# PowerBoard.net
KiCad netlist of a schematic drawn in EAGLE
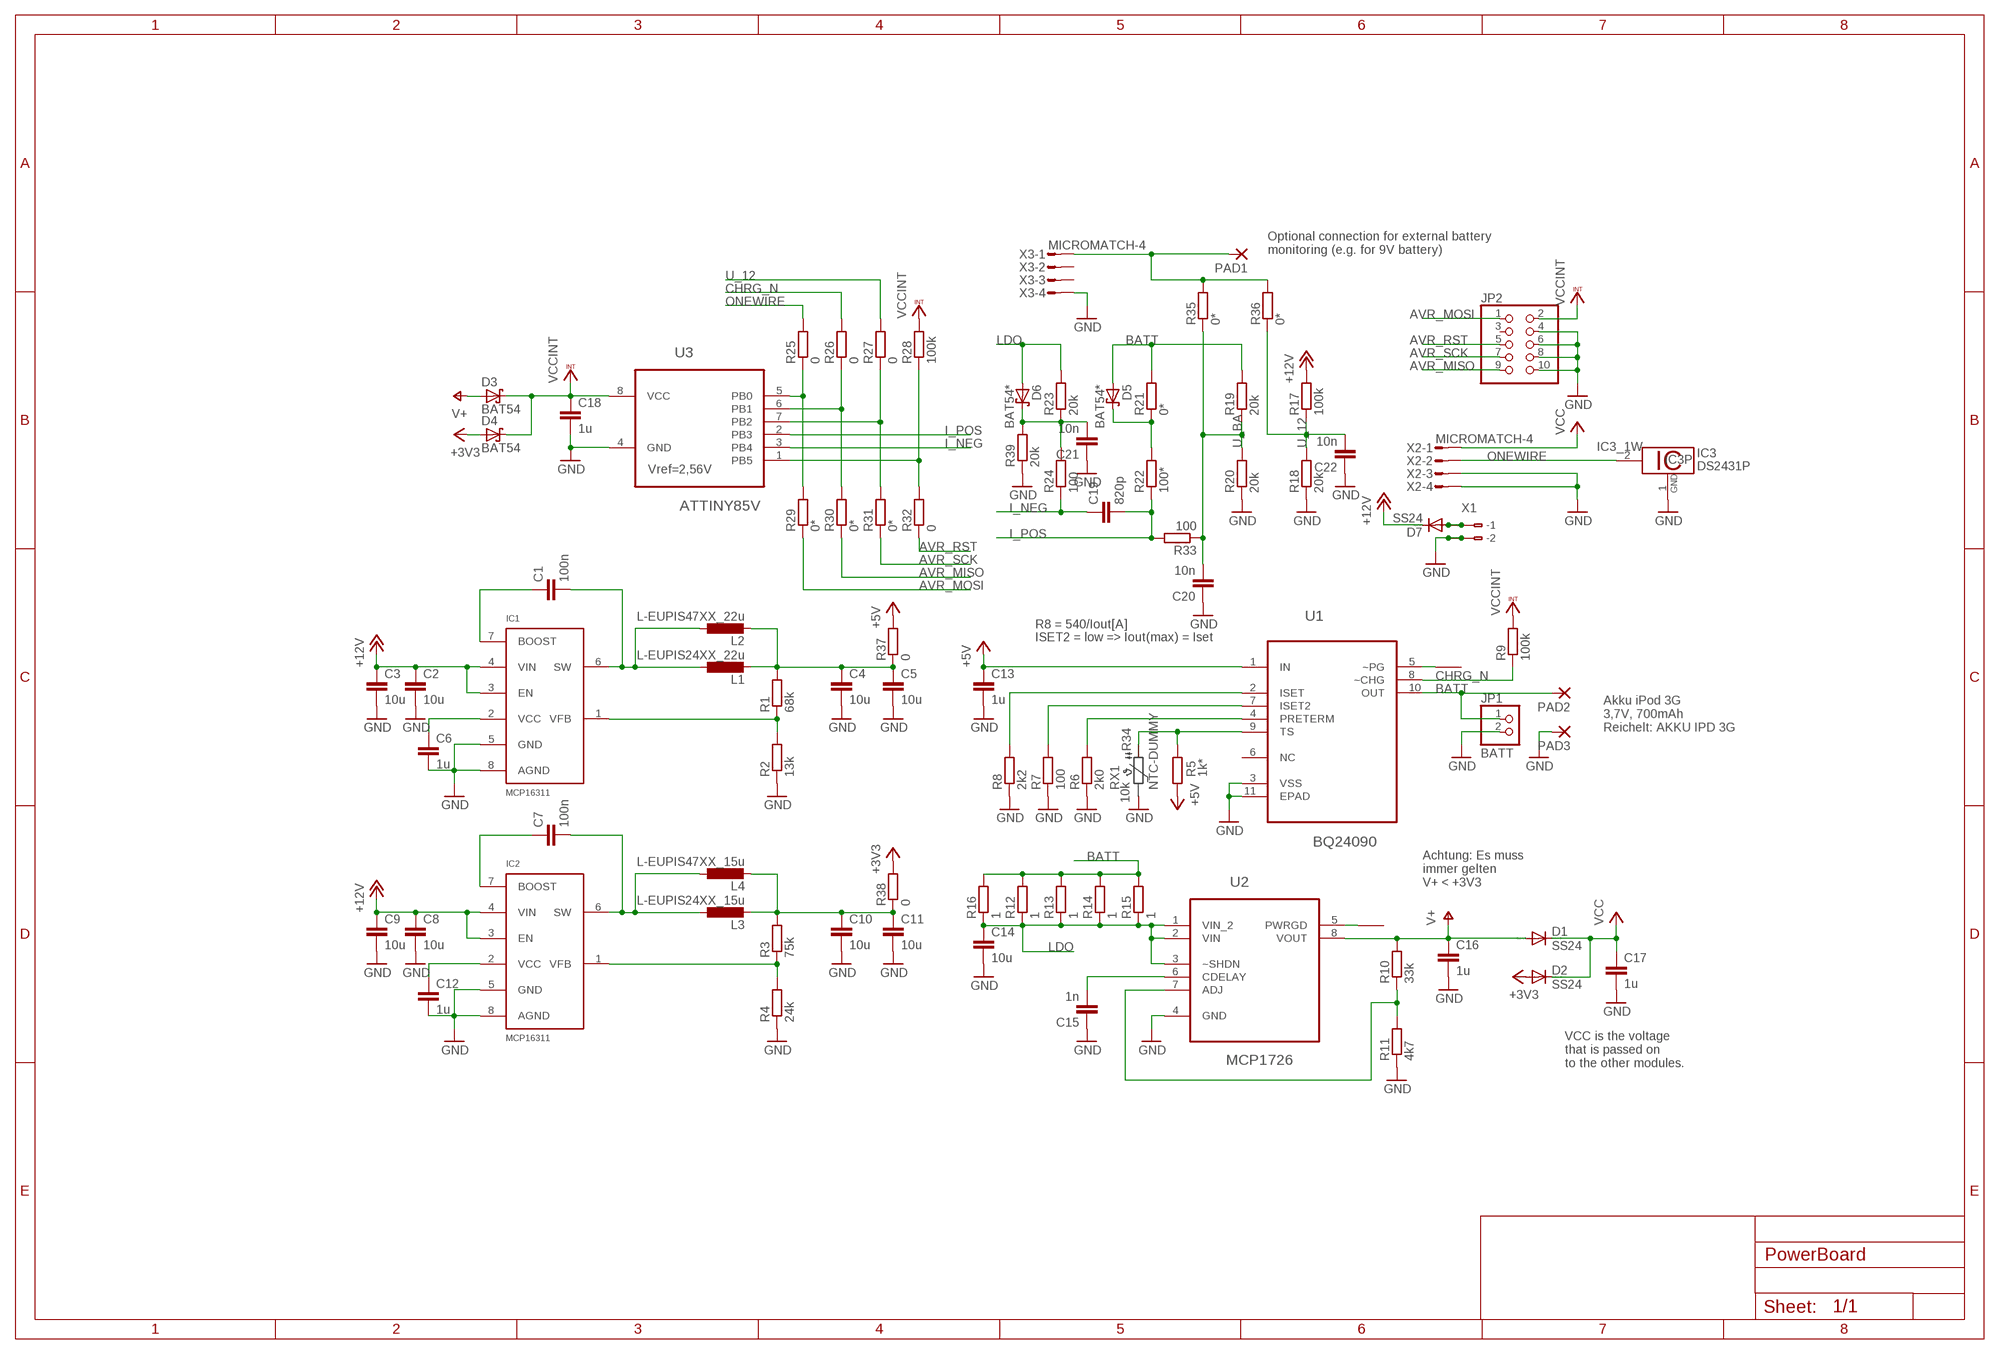
[diagram p0: schematic, sheet 1]

(export (version "E")
  (design (tool "Eeschema 10.0.6"))
  (components
    (comp (ref "C1")
      (value "100n")
      (footprint "eagle-import:C0603")
      (libsource (lib "eagle-import") (part "C-EUC0603"))
    )
    (comp (ref "C2")
      (value "10u")
      (footprint "eagle-import:C1210")
      (libsource (lib "eagle-import") (part "C-EUC1210"))
    )
    (comp (ref "C3")
      (value "10u")
      (footprint "eagle-import:C1210")
      (libsource (lib "eagle-import") (part "C-EUC1210"))
    )
    (comp (ref "C4")
      (value "10u")
      (footprint "eagle-import:C1210")
      (libsource (lib "eagle-import") (part "C-EUC1210"))
    )
    (comp (ref "C5")
      (value "10u")
      (footprint "eagle-import:C1210")
      (libsource (lib "eagle-import") (part "C-EUC1210"))
    )
    (comp (ref "C6")
      (value "1u")
      (footprint "eagle-import:C0603")
      (libsource (lib "eagle-import") (part "C-EUC0603"))
    )
    (comp (ref "C7")
      (value "100n")
      (footprint "eagle-import:C0603")
      (libsource (lib "eagle-import") (part "C-EUC0603"))
    )
    (comp (ref "C8")
      (value "10u")
      (footprint "eagle-import:C1210")
      (libsource (lib "eagle-import") (part "C-EUC1210"))
    )
    (comp (ref "C9")
      (value "10u")
      (footprint "eagle-import:C1210")
      (libsource (lib "eagle-import") (part "C-EUC1210"))
    )
    (comp (ref "C10")
      (value "10u")
      (footprint "eagle-import:C1210")
      (libsource (lib "eagle-import") (part "C-EUC1210"))
    )
    (comp (ref "C11")
      (value "10u")
      (footprint "eagle-import:C1210")
      (libsource (lib "eagle-import") (part "C-EUC1210"))
    )
    (comp (ref "C12")
      (value "1u")
      (footprint "eagle-import:C0603")
      (libsource (lib "eagle-import") (part "C-EUC0603"))
    )
    (comp (ref "C13")
      (value "1u")
      (footprint "eagle-import:C0603")
      (libsource (lib "eagle-import") (part "C-EUC0603"))
    )
    (comp (ref "C14")
      (value "10u")
      (footprint "eagle-import:C1210")
      (libsource (lib "eagle-import") (part "C-EUC1210"))
    )
    (comp (ref "C15")
      (value "1n")
      (footprint "eagle-import:C0603")
      (libsource (lib "eagle-import") (part "C-EUC0603"))
    )
    (comp (ref "C16")
      (value "1u")
      (footprint "eagle-import:C0603")
      (libsource (lib "eagle-import") (part "C-EUC0603"))
    )
    (comp (ref "C17")
      (value "1u")
      (footprint "eagle-import:C0603")
      (libsource (lib "eagle-import") (part "C-EUC0603"))
    )
    (comp (ref "C18")
      (value "1u")
      (footprint "eagle-import:C0603")
      (libsource (lib "eagle-import") (part "C-EUC0603"))
    )
    (comp (ref "C19")
      (value "820p")
      (footprint "eagle-import:C0603")
      (libsource (lib "eagle-import") (part "C-EUC0603"))
    )
    (comp (ref "C20")
      (value "10n")
      (footprint "eagle-import:C0603")
      (libsource (lib "eagle-import") (part "C-EUC0603"))
    )
    (comp (ref "C21")
      (value "10n")
      (footprint "eagle-import:C0603")
      (libsource (lib "eagle-import") (part "C-EUC0603"))
    )
    (comp (ref "C22")
      (value "10n")
      (footprint "eagle-import:C0603")
      (libsource (lib "eagle-import") (part "C-EUC0603"))
    )
    (comp (ref "D1")
      (value "SS24")
      (footprint "eagle-import:SMB")
      (libsource (lib "eagle-import") (part "DIODE-SMB"))
    )
    (comp (ref "D2")
      (value "SS24")
      (footprint "eagle-import:SMB")
      (libsource (lib "eagle-import") (part "DIODE-SMB"))
    )
    (comp (ref "D3")
      (value "BAT54")
      (footprint "eagle-import:SOT23")
      (libsource (lib "eagle-import") (part "BAT54"))
    )
    (comp (ref "D4")
      (value "BAT54")
      (footprint "eagle-import:SOT23")
      (libsource (lib "eagle-import") (part "BAT54"))
    )
    (comp (ref "D5")
      (value "BAT54*")
      (footprint "eagle-import:SOT23")
      (libsource (lib "eagle-import") (part "BAT54"))
    )
    (comp (ref "D6")
      (value "BAT54*")
      (footprint "eagle-import:SOT23")
      (libsource (lib "eagle-import") (part "BAT54"))
    )
    (comp (ref "D7")
      (value "SS24")
      (footprint "eagle-import:SMB")
      (libsource (lib "eagle-import") (part "DIODE-SMB"))
    )
    (comp (ref "IC1")
      (value "MCP16311")
      (footprint "eagle-import:SOP65P490X110-8N")
      (libsource (lib "eagle-import") (part "MCP16311"))
    )
    (comp (ref "IC2")
      (value "MCP16311")
      (footprint "eagle-import:SOP65P490X110-8N")
      (libsource (lib "eagle-import") (part "MCP16311"))
    )
    (comp (ref "IC3")
      (value "DS2431P")
      (footprint "eagle-import:TSOC6")
      (libsource (lib "eagle-import") (part "DS2431P"))
    )
    (comp (ref "JP1")
      (value "BATT")
      (footprint "eagle-import:1X02")
      (libsource (lib "eagle-import") (part "PINHD-1X2"))
    )
    (comp (ref "JP2")
      (value "PINHD-2X5")
      (footprint "eagle-import:2X05")
      (libsource (lib "eagle-import") (part "PINHD-2X5"))
    )
    (comp (ref "L1")
      (value "L-EUPIS24XX_22u")
      (footprint "eagle-import:PIS24XX")
      (libsource (lib "eagle-import") (part "L-EUPIS24XX"))
    )
    (comp (ref "L2")
      (value "L-EUPIS47XX_22u")
      (footprint "eagle-import:PIS47XX")
      (libsource (lib "eagle-import") (part "L-EUPIS47XX"))
    )
    (comp (ref "L3")
      (value "L-EUPIS24XX_15u")
      (footprint "eagle-import:PIS24XX")
      (libsource (lib "eagle-import") (part "L-EUPIS24XX"))
    )
    (comp (ref "L4")
      (value "L-EUPIS47XX_15u")
      (footprint "eagle-import:PIS47XX")
      (libsource (lib "eagle-import") (part "L-EUPIS47XX"))
    )
    (comp (ref "PAD1")
      (value "WIREPADSMD2,54-5,08")
      (footprint "eagle-import:SMD2,54-5,08")
      (libsource (lib "eagle-import") (part "WIREPADSMD2,54-5,08"))
    )
    (comp (ref "PAD2")
      (value "WIREPADSMD2,54-5,08")
      (footprint "eagle-import:SMD2,54-5,08")
      (libsource (lib "eagle-import") (part "WIREPADSMD2,54-5,08"))
    )
    (comp (ref "PAD3")
      (value "WIREPADSMD2,54-5,08")
      (footprint "eagle-import:SMD2,54-5,08")
      (libsource (lib "eagle-import") (part "WIREPADSMD2,54-5,08"))
    )
    (comp (ref "R1")
      (value "68k")
      (footprint "eagle-import:R0603")
      (libsource (lib "eagle-import") (part "R-EU_R0603"))
    )
    (comp (ref "R2")
      (value "13k")
      (footprint "eagle-import:R0603")
      (libsource (lib "eagle-import") (part "R-EU_R0603"))
    )
    (comp (ref "R3")
      (value "75k")
      (footprint "eagle-import:R0603")
      (libsource (lib "eagle-import") (part "R-EU_R0603"))
    )
    (comp (ref "R4")
      (value "24k")
      (footprint "eagle-import:R0603")
      (libsource (lib "eagle-import") (part "R-EU_R0603"))
    )
    (comp (ref "R5")
      (value "1k*")
      (footprint "eagle-import:R0603")
      (libsource (lib "eagle-import") (part "R-EU_R0603"))
    )
    (comp (ref "R6")
      (value "2k0")
      (footprint "eagle-import:R0603")
      (libsource (lib "eagle-import") (part "R-EU_R0603"))
    )
    (comp (ref "R7")
      (value "100")
      (footprint "eagle-import:R0603")
      (libsource (lib "eagle-import") (part "R-EU_R0603"))
    )
    (comp (ref "R8")
      (value "2k2")
      (footprint "eagle-import:R0603")
      (libsource (lib "eagle-import") (part "R-EU_R0603"))
    )
    (comp (ref "R9")
      (value "100k")
      (footprint "eagle-import:R0603")
      (libsource (lib "eagle-import") (part "R-EU_R0603"))
    )
    (comp (ref "R10")
      (value "33k")
      (footprint "eagle-import:R0603")
      (libsource (lib "eagle-import") (part "R-EU_R0603"))
    )
    (comp (ref "R11")
      (value "4k7")
      (footprint "eagle-import:R0603")
      (libsource (lib "eagle-import") (part "R-EU_R0603"))
    )
    (comp (ref "R12")
      (value "1")
      (footprint "eagle-import:R0402")
      (libsource (lib "eagle-import") (part "R-EU_R0402"))
    )
    (comp (ref "R13")
      (value "1")
      (footprint "eagle-import:R0402")
      (libsource (lib "eagle-import") (part "R-EU_R0402"))
    )
    (comp (ref "R14")
      (value "1")
      (footprint "eagle-import:R0402")
      (libsource (lib "eagle-import") (part "R-EU_R0402"))
    )
    (comp (ref "R15")
      (value "1")
      (footprint "eagle-import:R0402")
      (libsource (lib "eagle-import") (part "R-EU_R0402"))
    )
    (comp (ref "R16")
      (value "1")
      (footprint "eagle-import:R0402")
      (libsource (lib "eagle-import") (part "R-EU_R0402"))
    )
    (comp (ref "R17")
      (value "100k")
      (footprint "eagle-import:R0603")
      (libsource (lib "eagle-import") (part "R-EU_R0603"))
    )
    (comp (ref "R18")
      (value "20k")
      (footprint "eagle-import:R0603")
      (libsource (lib "eagle-import") (part "R-EU_R0603"))
    )
    (comp (ref "R19")
      (value "20k")
      (footprint "eagle-import:R0603")
      (libsource (lib "eagle-import") (part "R-EU_R0603"))
    )
    (comp (ref "R20")
      (value "20k")
      (footprint "eagle-import:R0603")
      (libsource (lib "eagle-import") (part "R-EU_R0603"))
    )
    (comp (ref "R21")
      (value "0*")
      (footprint "eagle-import:R0603")
      (libsource (lib "eagle-import") (part "R-EU_R0603"))
    )
    (comp (ref "R22")
      (value "100*")
      (footprint "eagle-import:R0603")
      (libsource (lib "eagle-import") (part "R-EU_R0603"))
    )
    (comp (ref "R23")
      (value "20k")
      (footprint "eagle-import:R0603")
      (libsource (lib "eagle-import") (part "R-EU_R0603"))
    )
    (comp (ref "R24")
      (value "100")
      (footprint "eagle-import:R0603")
      (libsource (lib "eagle-import") (part "R-EU_R0603"))
    )
    (comp (ref "R25")
      (value "0")
      (footprint "eagle-import:R0402")
      (libsource (lib "eagle-import") (part "R-EU_R0402"))
    )
    (comp (ref "R26")
      (value "0")
      (footprint "eagle-import:R0402")
      (libsource (lib "eagle-import") (part "R-EU_R0402"))
    )
    (comp (ref "R27")
      (value "0")
      (footprint "eagle-import:R0402")
      (libsource (lib "eagle-import") (part "R-EU_R0402"))
    )
    (comp (ref "R28")
      (value "100k")
      (footprint "eagle-import:R0402")
      (libsource (lib "eagle-import") (part "R-EU_R0402"))
    )
    (comp (ref "R29")
      (value "0*")
      (footprint "eagle-import:R0402")
      (libsource (lib "eagle-import") (part "R-EU_R0402"))
    )
    (comp (ref "R30")
      (value "0*")
      (footprint "eagle-import:R0402")
      (libsource (lib "eagle-import") (part "R-EU_R0402"))
    )
    (comp (ref "R31")
      (value "0*")
      (footprint "eagle-import:R0402")
      (libsource (lib "eagle-import") (part "R-EU_R0402"))
    )
    (comp (ref "R32")
      (value "0")
      (footprint "eagle-import:R0402")
      (libsource (lib "eagle-import") (part "R-EU_R0402"))
    )
    (comp (ref "R33")
      (value "100")
      (footprint "eagle-import:R0603")
      (libsource (lib "eagle-import") (part "R-EU_R0603"))
    )
    (comp (ref "R34")
      (value "10k")
      (footprint "eagle-import:R0603")
      (libsource (lib "eagle-import") (part "R-EU_R0603"))
    )
    (comp (ref "R35")
      (value "0*")
      (footprint "eagle-import:R0603")
      (libsource (lib "eagle-import") (part "R-EU_R0603"))
    )
    (comp (ref "R36")
      (value "0*")
      (footprint "eagle-import:R0603")
      (libsource (lib "eagle-import") (part "R-EU_R0603"))
    )
    (comp (ref "R37")
      (value "0")
      (footprint "eagle-import:R0603")
      (libsource (lib "eagle-import") (part "R-EU_R0603"))
    )
    (comp (ref "R38")
      (value "0")
      (footprint "eagle-import:R0603")
      (libsource (lib "eagle-import") (part "R-EU_R0603"))
    )
    (comp (ref "R39")
      (value "20k")
      (footprint "eagle-import:R0603")
      (libsource (lib "eagle-import") (part "R-EU_R0603"))
    )
    (comp (ref "U$1")
      (value "PAD100-RND")
      (footprint "eagle-import:PAD-100-RND")
      (libsource (lib "eagle-import") (part "PAD100-RND"))
    )
    (comp (ref "U$3")
      (value "PAD100-RND")
      (footprint "eagle-import:PAD-100-RND")
      (libsource (lib "eagle-import") (part "PAD100-RND"))
    )
    (comp (ref "U1")
      (value "BQ24090")
      (footprint "eagle-import:SOP50P490X110-11N")
      (fields (field (name "MF") "Texas Instruments") (field (name "MP") "BQ24090DGQT"))
      (libsource (lib "eagle-import") (part "BQ24090DGQT"))
    )
    (comp (ref "U2")
      (value "MCP1726")
      (footprint "eagle-import:SOIC127P490X175-8N")
      (fields (field (name "MF") "Microchip") (field (name "MP") "MCP1726-3302E/SN"))
      (libsource (lib "eagle-import") (part "MCP1726-3302E/SN"))
    )
    (comp (ref "U3")
      (value "ATTINY85V")
      (footprint "eagle-import:SOIC127P798X216-8N")
      (fields (field (name "MF") "Atmel") (field (name "MP") "ATTINY85V-10SU"))
      (libsource (lib "eagle-import") (part "ATTINY85V-10SU"))
    )
    (comp (ref "X1")
      (value "233-102")
      (footprint "eagle-import:233-102")
      (libsource (lib "eagle-import") (part "233-102"))
    )
    (comp (ref "X2")
      (value "MICROMATCH-4")
      (footprint "eagle-import:MICROMATCH-4")
      (fields (field (name "MPN") "7-215464-4"))
      (libsource (lib "eagle-import") (part "MICROMATCH-4"))
    )
    (comp (ref "X3")
      (value "MICROMATCH-4")
      (footprint "eagle-import:MICROMATCH-4")
      (fields (field (name "MPN") "7-215464-4"))
      (libsource (lib "eagle-import") (part "MICROMATCH-4"))
    )
  )
  (nets
    (net (code "1") (name "+3V3") (class "Default")
      (node (ref "D2") (pin "A") (pinfunction "A_A") (pintype "passive"))
      (node (ref "D4") (pin "1") (pinfunction "A_1") (pintype "passive"))
      (node (ref "R38") (pin "2") (pinfunction "2_2") (pintype "passive"))
    )
    (net (code "2") (name "+5V") (class "Default")
      (node (ref "C13") (pin "1") (pinfunction "1_1") (pintype "passive"))
      (node (ref "R37") (pin "2") (pinfunction "2_2") (pintype "passive"))
      (node (ref "R5") (pin "1") (pinfunction "1_1") (pintype "passive"))
      (node (ref "U1") (pin "1") (pinfunction "IN_1") (pintype "input"))
    )
    (net (code "3") (name "+12V") (class "Default")
      (node (ref "C2") (pin "1") (pinfunction "1_1") (pintype "passive"))
      (node (ref "C3") (pin "1") (pinfunction "1_1") (pintype "passive"))
      (node (ref "C8") (pin "1") (pinfunction "1_1") (pintype "passive"))
      (node (ref "C9") (pin "1") (pinfunction "1_1") (pintype "passive"))
      (node (ref "D7") (pin "C") (pinfunction "C_C") (pintype "passive"))
      (node (ref "IC1") (pin "3") (pinfunction "EN_3") (pintype "bidirectional"))
      (node (ref "IC1") (pin "4") (pinfunction "VIN_4") (pintype "bidirectional"))
      (node (ref "IC2") (pin "3") (pinfunction "EN_3") (pintype "bidirectional"))
      (node (ref "IC2") (pin "4") (pinfunction "VIN_4") (pintype "bidirectional"))
      (node (ref "R17") (pin "2") (pinfunction "2_2") (pintype "passive"))
    )
    (net (code "4") (name "/AVR_MISO") (class "Default")
      (node (ref "JP2") (pin "9") (pinfunction "9_9") (pintype "passive"))
      (node (ref "R30") (pin "1") (pinfunction "1_1") (pintype "passive"))
    )
    (net (code "5") (name "/AVR_MOSI") (class "Default")
      (node (ref "JP2") (pin "1") (pinfunction "1_1") (pintype "passive"))
      (node (ref "R29") (pin "1") (pinfunction "1_1") (pintype "passive"))
    )
    (net (code "6") (name "/AVR_RST") (class "Default")
      (node (ref "JP2") (pin "5") (pinfunction "5_5") (pintype "passive"))
      (node (ref "R32") (pin "1") (pinfunction "1_1") (pintype "passive"))
    )
    (net (code "7") (name "/AVR_SCK") (class "Default")
      (node (ref "JP2") (pin "7") (pinfunction "7_7") (pintype "passive"))
      (node (ref "R31") (pin "1") (pinfunction "1_1") (pintype "passive"))
    )
    (net (code "8") (name "/BATT") (class "Default")
      (node (ref "D5") (pin "1") (pinfunction "A_1") (pintype "passive"))
      (node (ref "JP1") (pin "1") (pinfunction "1_1") (pintype "passive"))
      (node (ref "PAD2") (pin "1") (pinfunction "P_1") (pintype "passive"))
      (node (ref "R12") (pin "2") (pinfunction "2_2") (pintype "passive"))
      (node (ref "R13") (pin "2") (pinfunction "2_2") (pintype "passive"))
      (node (ref "R14") (pin "2") (pinfunction "2_2") (pintype "passive"))
      (node (ref "R15") (pin "2") (pinfunction "2_2") (pintype "passive"))
      (node (ref "R16") (pin "2") (pinfunction "2_2") (pintype "passive"))
      (node (ref "R19") (pin "2") (pinfunction "2_2") (pintype "passive"))
      (node (ref "R21") (pin "2") (pinfunction "2_2") (pintype "passive"))
      (node (ref "U1") (pin "10") (pinfunction "OUT_10") (pintype "output"))
    )
    (net (code "9") (name "/CHRG_N") (class "Default")
      (node (ref "R26") (pin "2") (pinfunction "2_2") (pintype "passive"))
      (node (ref "R9") (pin "1") (pinfunction "1_1") (pintype "passive"))
      (node (ref "U1") (pin "8") (pinfunction "~{CHG}_8") (pintype "output"))
    )
    (net (code "10") (name "/I_NEG") (class "Default")
      (node (ref "C19") (pin "1") (pinfunction "1_1") (pintype "passive"))
      (node (ref "R24") (pin "1") (pinfunction "1_1") (pintype "passive"))
      (node (ref "U3") (pin "3") (pinfunction "PB4_3") (pintype "bidirectional"))
    )
    (net (code "11") (name "/I_POS") (class "Default")
      (node (ref "C19") (pin "2") (pinfunction "2_2") (pintype "passive"))
      (node (ref "R22") (pin "1") (pinfunction "1_1") (pintype "passive"))
      (node (ref "R33") (pin "2") (pinfunction "2_2") (pintype "passive"))
      (node (ref "U3") (pin "2") (pinfunction "PB3_2") (pintype "bidirectional"))
    )
    (net (code "12") (name "/LDO") (class "Default")
      (node (ref "C14") (pin "1") (pinfunction "1_1") (pintype "passive"))
      (node (ref "D6") (pin "1") (pinfunction "A_1") (pintype "passive"))
      (node (ref "R12") (pin "1") (pinfunction "1_1") (pintype "passive"))
      (node (ref "R13") (pin "1") (pinfunction "1_1") (pintype "passive"))
      (node (ref "R14") (pin "1") (pinfunction "1_1") (pintype "passive"))
      (node (ref "R15") (pin "1") (pinfunction "1_1") (pintype "passive"))
      (node (ref "R16") (pin "1") (pinfunction "1_1") (pintype "passive"))
      (node (ref "R23") (pin "2") (pinfunction "2_2") (pintype "passive"))
      (node (ref "U2") (pin "1") (pinfunction "VIN_2_1") (pintype "power_in"))
      (node (ref "U2") (pin "2") (pinfunction "VIN_2") (pintype "power_in"))
      (node (ref "U2") (pin "3") (pinfunction "~{SHDN}_3") (pintype "input"))
    )
    (net (code "13") (name "/ONEWIRE") (class "Default")
      (node (ref "IC3") (pin "2") (pinfunction "1W_2") (pintype "power_in"))
      (node (ref "R25") (pin "2") (pinfunction "2_2") (pintype "passive"))
      (node (ref "X2") (pin "2") (pinfunction "S_2") (pintype "passive"))
    )
    (net (code "14") (name "/U_12") (class "Default")
      (node (ref "C22") (pin "2") (pinfunction "2_2") (pintype "passive"))
      (node (ref "R17") (pin "1") (pinfunction "1_1") (pintype "passive"))
      (node (ref "R18") (pin "2") (pinfunction "2_2") (pintype "passive"))
      (node (ref "R27") (pin "2") (pinfunction "2_2") (pintype "passive"))
      (node (ref "R36") (pin "1") (pinfunction "1_1") (pintype "passive"))
    )
    (net (code "15") (name "/U_BA") (class "Default")
      (node (ref "C20") (pin "2") (pinfunction "2_2") (pintype "passive"))
      (node (ref "R19") (pin "1") (pinfunction "1_1") (pintype "passive"))
      (node (ref "R20") (pin "2") (pinfunction "2_2") (pintype "passive"))
      (node (ref "R33") (pin "1") (pinfunction "1_1") (pintype "passive"))
      (node (ref "R35") (pin "1") (pinfunction "1_1") (pintype "passive"))
    )
    (net (code "16") (name "GND") (class "Default")
      (node (ref "C10") (pin "2") (pinfunction "2_2") (pintype "passive"))
      (node (ref "C11") (pin "2") (pinfunction "2_2") (pintype "passive"))
      (node (ref "C12") (pin "2") (pinfunction "2_2") (pintype "passive"))
      (node (ref "C13") (pin "2") (pinfunction "2_2") (pintype "passive"))
      (node (ref "C14") (pin "2") (pinfunction "2_2") (pintype "passive"))
      (node (ref "C15") (pin "1") (pinfunction "1_1") (pintype "passive"))
      (node (ref "C16") (pin "2") (pinfunction "2_2") (pintype "passive"))
      (node (ref "C17") (pin "2") (pinfunction "2_2") (pintype "passive"))
      (node (ref "C18") (pin "2") (pinfunction "2_2") (pintype "passive"))
      (node (ref "C2") (pin "2") (pinfunction "2_2") (pintype "passive"))
      (node (ref "C20") (pin "1") (pinfunction "1_1") (pintype "passive"))
      (node (ref "C21") (pin "1") (pinfunction "1_1") (pintype "passive"))
      (node (ref "C22") (pin "1") (pinfunction "1_1") (pintype "passive"))
      (node (ref "C3") (pin "2") (pinfunction "2_2") (pintype "passive"))
      (node (ref "C4") (pin "2") (pinfunction "2_2") (pintype "passive"))
      (node (ref "C5") (pin "2") (pinfunction "2_2") (pintype "passive"))
      (node (ref "C6") (pin "2") (pinfunction "2_2") (pintype "passive"))
      (node (ref "C8") (pin "2") (pinfunction "2_2") (pintype "passive"))
      (node (ref "C9") (pin "2") (pinfunction "2_2") (pintype "passive"))
      (node (ref "IC1") (pin "5") (pinfunction "GND_5") (pintype "bidirectional"))
      (node (ref "IC1") (pin "8") (pinfunction "AGND_8") (pintype "bidirectional"))
      (node (ref "IC2") (pin "5") (pinfunction "GND_5") (pintype "bidirectional"))
      (node (ref "IC2") (pin "8") (pinfunction "AGND_8") (pintype "bidirectional"))
      (node (ref "IC3") (pin "1") (pinfunction "GND_1") (pintype "power_in"))
      (node (ref "JP1") (pin "2") (pinfunction "2_2") (pintype "passive"))
      (node (ref "JP2") (pin "10") (pinfunction "10_10") (pintype "passive"))
      (node (ref "JP2") (pin "4") (pinfunction "4_4") (pintype "passive"))
      (node (ref "JP2") (pin "6") (pinfunction "6_6") (pintype "passive"))
      (node (ref "JP2") (pin "8") (pinfunction "8_8") (pintype "passive"))
      (node (ref "PAD3") (pin "1") (pinfunction "P_1") (pintype "passive"))
      (node (ref "R11") (pin "1") (pinfunction "1_1") (pintype "passive"))
      (node (ref "R18") (pin "1") (pinfunction "1_1") (pintype "passive"))
      (node (ref "R2") (pin "1") (pinfunction "1_1") (pintype "passive"))
      (node (ref "R20") (pin "1") (pinfunction "1_1") (pintype "passive"))
      (node (ref "R34") (pin "1") (pinfunction "1_1") (pintype "passive"))
      (node (ref "R39") (pin "1") (pinfunction "1_1") (pintype "passive"))
      (node (ref "R4") (pin "1") (pinfunction "1_1") (pintype "passive"))
      (node (ref "R6") (pin "1") (pinfunction "1_1") (pintype "passive"))
      (node (ref "R7") (pin "1") (pinfunction "1_1") (pintype "passive"))
      (node (ref "R8") (pin "1") (pinfunction "1_1") (pintype "passive"))
      (node (ref "U1") (pin "11") (pinfunction "EPAD_11") (pintype "passive"))
      (node (ref "U1") (pin "3") (pinfunction "VSS_3") (pintype "power_in"))
      (node (ref "U2") (pin "4") (pinfunction "GND_4") (pintype "passive"))
      (node (ref "U3") (pin "4") (pinfunction "GND_4") (pintype "passive"))
      (node (ref "X1") (pin "A2") (pinfunction "-2_A2") (pintype "passive"))
      (node (ref "X1") (pin "B2") (pinfunction "B-2_B2") (pintype "passive"))
      (node (ref "X2") (pin "3") (pinfunction "S_3") (pintype "passive"))
      (node (ref "X2") (pin "4") (pinfunction "S_4") (pintype "passive"))
      (node (ref "X3") (pin "4") (pinfunction "S_4") (pintype "passive"))
    )
    (net (code "17") (name "Net-(D5-C)") (class "Default")
      (node (ref "D5") (pin "3") (pinfunction "C_3") (pintype "passive"))
      (node (ref "R21") (pin "1") (pinfunction "1_1") (pintype "passive"))
      (node (ref "R22") (pin "2") (pinfunction "2_2") (pintype "passive"))
    )
    (net (code "18") (name "Net-(D6-C)") (class "Default")
      (node (ref "C21") (pin "2") (pinfunction "2_2") (pintype "passive"))
      (node (ref "D6") (pin "3") (pinfunction "C_3") (pintype "passive"))
      (node (ref "R23") (pin "1") (pinfunction "1_1") (pintype "passive"))
      (node (ref "R24") (pin "2") (pinfunction "2_2") (pintype "passive"))
      (node (ref "R39") (pin "2") (pinfunction "2_2") (pintype "passive"))
    )
    (net (code "19") (name "Net-(IC1-BOOST)") (class "Default")
      (node (ref "C1") (pin "1") (pinfunction "1_1") (pintype "passive"))
      (node (ref "IC1") (pin "7") (pinfunction "BOOST_7") (pintype "bidirectional"))
    )
    (net (code "20") (name "Net-(IC1-SW)") (class "Default")
      (node (ref "C1") (pin "2") (pinfunction "2_2") (pintype "passive"))
      (node (ref "IC1") (pin "6") (pinfunction "SW_6") (pintype "bidirectional"))
      (node (ref "L1") (pin "2") (pinfunction "1_2") (pintype "passive"))
      (node (ref "L2") (pin "2") (pinfunction "1_2") (pintype "passive"))
    )
    (net (code "21") (name "Net-(IC1-VCC)") (class "Default")
      (node (ref "C6") (pin "1") (pinfunction "1_1") (pintype "passive"))
      (node (ref "IC1") (pin "2") (pinfunction "VCC_2") (pintype "bidirectional"))
    )
    (net (code "22") (name "Net-(IC1-VFB)") (class "Default")
      (node (ref "IC1") (pin "1") (pinfunction "VFB_1") (pintype "bidirectional"))
      (node (ref "R1") (pin "1") (pinfunction "1_1") (pintype "passive"))
      (node (ref "R2") (pin "2") (pinfunction "2_2") (pintype "passive"))
    )
    (net (code "23") (name "Net-(IC2-BOOST)") (class "Default")
      (node (ref "C7") (pin "1") (pinfunction "1_1") (pintype "passive"))
      (node (ref "IC2") (pin "7") (pinfunction "BOOST_7") (pintype "bidirectional"))
    )
    (net (code "24") (name "Net-(IC2-SW)") (class "Default")
      (node (ref "C7") (pin "2") (pinfunction "2_2") (pintype "passive"))
      (node (ref "IC2") (pin "6") (pinfunction "SW_6") (pintype "bidirectional"))
      (node (ref "L3") (pin "2") (pinfunction "1_2") (pintype "passive"))
      (node (ref "L4") (pin "2") (pinfunction "1_2") (pintype "passive"))
    )
    (net (code "25") (name "Net-(IC2-VCC)") (class "Default")
      (node (ref "C12") (pin "1") (pinfunction "1_1") (pintype "passive"))
      (node (ref "IC2") (pin "2") (pinfunction "VCC_2") (pintype "bidirectional"))
    )
    (net (code "26") (name "Net-(IC2-VFB)") (class "Default")
      (node (ref "IC2") (pin "1") (pinfunction "VFB_1") (pintype "bidirectional"))
      (node (ref "R3") (pin "1") (pinfunction "1_1") (pintype "passive"))
      (node (ref "R4") (pin "2") (pinfunction "2_2") (pintype "passive"))
    )
    (net (code "27") (name "Net-(L1-2)") (class "Default")
      (node (ref "C4") (pin "1") (pinfunction "1_1") (pintype "passive"))
      (node (ref "C5") (pin "1") (pinfunction "1_1") (pintype "passive"))
      (node (ref "L1") (pin "1") (pinfunction "2_1") (pintype "passive"))
      (node (ref "L2") (pin "1") (pinfunction "2_1") (pintype "passive"))
      (node (ref "R1") (pin "2") (pinfunction "2_2") (pintype "passive"))
      (node (ref "R37") (pin "1") (pinfunction "1_1") (pintype "passive"))
    )
    (net (code "28") (name "Net-(L3-2)") (class "Default")
      (node (ref "C10") (pin "1") (pinfunction "1_1") (pintype "passive"))
      (node (ref "C11") (pin "1") (pinfunction "1_1") (pintype "passive"))
      (node (ref "L3") (pin "1") (pinfunction "2_1") (pintype "passive"))
      (node (ref "L4") (pin "1") (pinfunction "2_1") (pintype "passive"))
      (node (ref "R3") (pin "2") (pinfunction "2_2") (pintype "passive"))
      (node (ref "R38") (pin "1") (pinfunction "1_1") (pintype "passive"))
    )
    (net (code "29") (name "Net-(PAD1-P)") (class "Default")
      (node (ref "PAD1") (pin "1") (pinfunction "P_1") (pintype "passive"))
      (node (ref "R35") (pin "2") (pinfunction "2_2") (pintype "passive"))
      (node (ref "R36") (pin "2") (pinfunction "2_2") (pintype "passive"))
      (node (ref "X3") (pin "1") (pinfunction "S_1") (pintype "passive"))
    )
    (net (code "30") (name "Net-(U1-ISET)") (class "Default")
      (node (ref "R8") (pin "2") (pinfunction "2_2") (pintype "passive"))
      (node (ref "U1") (pin "2") (pinfunction "ISET_2") (pintype "input"))
    )
    (net (code "31") (name "Net-(U1-ISET2)") (class "Default")
      (node (ref "R7") (pin "2") (pinfunction "2_2") (pintype "passive"))
      (node (ref "U1") (pin "7") (pinfunction "ISET2_7") (pintype "input"))
    )
    (net (code "32") (name "Net-(U1-PRETERM)") (class "Default")
      (node (ref "R6") (pin "2") (pinfunction "2_2") (pintype "passive"))
      (node (ref "U1") (pin "4") (pinfunction "PRETERM_4") (pintype "input"))
    )
    (net (code "33") (name "Net-(U1-TS)") (class "Default")
      (node (ref "R34") (pin "2") (pinfunction "2_2") (pintype "passive"))
      (node (ref "R5") (pin "2") (pinfunction "2_2") (pintype "passive"))
      (node (ref "U1") (pin "9") (pinfunction "TS_9") (pintype "input"))
    )
    (net (code "34") (name "Net-(U1-~{PG})") (class "Default")
      (node (ref "U$1") (pin "P$1") (pinfunction "P$1_P$1") (pintype "bidirectional"))
      (node (ref "U1") (pin "5") (pinfunction "~{PG}_5") (pintype "output"))
    )
    (net (code "35") (name "Net-(U2-ADJ)") (class "Default")
      (node (ref "R10") (pin "1") (pinfunction "1_1") (pintype "passive"))
      (node (ref "R11") (pin "2") (pinfunction "2_2") (pintype "passive"))
      (node (ref "U2") (pin "7") (pinfunction "ADJ_7") (pintype "input"))
    )
    (net (code "36") (name "Net-(U2-CDELAY)") (class "Default")
      (node (ref "C15") (pin "2") (pinfunction "2_2") (pintype "passive"))
      (node (ref "U2") (pin "6") (pinfunction "CDELAY_6") (pintype "input"))
    )
    (net (code "37") (name "Net-(U2-PWRGD)") (class "Default")
      (node (ref "U$3") (pin "P$1") (pinfunction "P$1_P$1") (pintype "bidirectional"))
      (node (ref "U2") (pin "5") (pinfunction "PWRGD_5") (pintype "output"))
    )
    (net (code "38") (name "Net-(U3-PB0)") (class "Default")
      (node (ref "R25") (pin "1") (pinfunction "1_1") (pintype "passive"))
      (node (ref "R29") (pin "2") (pinfunction "2_2") (pintype "passive"))
      (node (ref "U3") (pin "5") (pinfunction "PB0_5") (pintype "bidirectional"))
    )
    (net (code "39") (name "Net-(U3-PB1)") (class "Default")
      (node (ref "R26") (pin "1") (pinfunction "1_1") (pintype "passive"))
      (node (ref "R30") (pin "2") (pinfunction "2_2") (pintype "passive"))
      (node (ref "U3") (pin "6") (pinfunction "PB1_6") (pintype "bidirectional"))
    )
    (net (code "40") (name "Net-(U3-PB2)") (class "Default")
      (node (ref "R27") (pin "1") (pinfunction "1_1") (pintype "passive"))
      (node (ref "R31") (pin "2") (pinfunction "2_2") (pintype "passive"))
      (node (ref "U3") (pin "7") (pinfunction "PB2_7") (pintype "bidirectional"))
    )
    (net (code "41") (name "Net-(U3-PB5)") (class "Default")
      (node (ref "R28") (pin "1") (pinfunction "1_1") (pintype "passive"))
      (node (ref "R32") (pin "2") (pinfunction "2_2") (pintype "passive"))
      (node (ref "U3") (pin "1") (pinfunction "PB5_1") (pintype "bidirectional"))
    )
    (net (code "42") (name "Net-(X1--1)") (class "Default")
      (node (ref "D7") (pin "A") (pinfunction "A_A") (pintype "passive"))
      (node (ref "X1") (pin "A1") (pinfunction "-1_A1") (pintype "passive"))
      (node (ref "X1") (pin "B1") (pinfunction "B-1_B1") (pintype "passive"))
    )
    (net (code "43") (name "V+") (class "Default")
      (node (ref "C16") (pin "1") (pinfunction "1_1") (pintype "passive"))
      (node (ref "D1") (pin "A") (pinfunction "A_A") (pintype "passive"))
      (node (ref "D3") (pin "1") (pinfunction "A_1") (pintype "passive"))
      (node (ref "R10") (pin "2") (pinfunction "2_2") (pintype "passive"))
      (node (ref "U2") (pin "8") (pinfunction "VOUT_8") (pintype "output"))
    )
    (net (code "44") (name "VCC") (class "Default")
      (node (ref "C17") (pin "1") (pinfunction "1_1") (pintype "passive"))
      (node (ref "D1") (pin "C") (pinfunction "C_C") (pintype "passive"))
      (node (ref "D2") (pin "C") (pinfunction "C_C") (pintype "passive"))
      (node (ref "X2") (pin "1") (pinfunction "S_1") (pintype "passive"))
    )
    (net (code "45") (name "VCCINT") (class "Default")
      (node (ref "C18") (pin "1") (pinfunction "1_1") (pintype "passive"))
      (node (ref "D3") (pin "3") (pinfunction "C_3") (pintype "passive"))
      (node (ref "D4") (pin "3") (pinfunction "C_3") (pintype "passive"))
      (node (ref "JP2") (pin "2") (pinfunction "2_2") (pintype "passive"))
      (node (ref "R28") (pin "2") (pinfunction "2_2") (pintype "passive"))
      (node (ref "R9") (pin "2") (pinfunction "2_2") (pintype "passive"))
      (node (ref "U3") (pin "8") (pinfunction "VCC_8") (pintype "power_in"))
    )
    (net (code "46") (name "unconnected-(JP2-Pad3)") (class "Default")
      (node (ref "JP2") (pin "3") (pinfunction "3_3") (pintype "passive"))
    )
    (net (code "47") (name "unconnected-(U1-NC-Pad6)") (class "Default")
      (node (ref "U1") (pin "6") (pinfunction "NC_6") (pintype "no_connect"))
    )
    (net (code "48") (name "unconnected-(X3B-S-Pad2)") (class "Default")
      (node (ref "X3") (pin "2") (pinfunction "S_2") (pintype "passive"))
    )
    (net (code "49") (name "unconnected-(X3C-S-Pad3)") (class "Default")
      (node (ref "X3") (pin "3") (pinfunction "S_3") (pintype "passive"))
    )
  )
)
